# 3_-MCU.net
KiCad netlist of a schematic drawn in Altium Designer
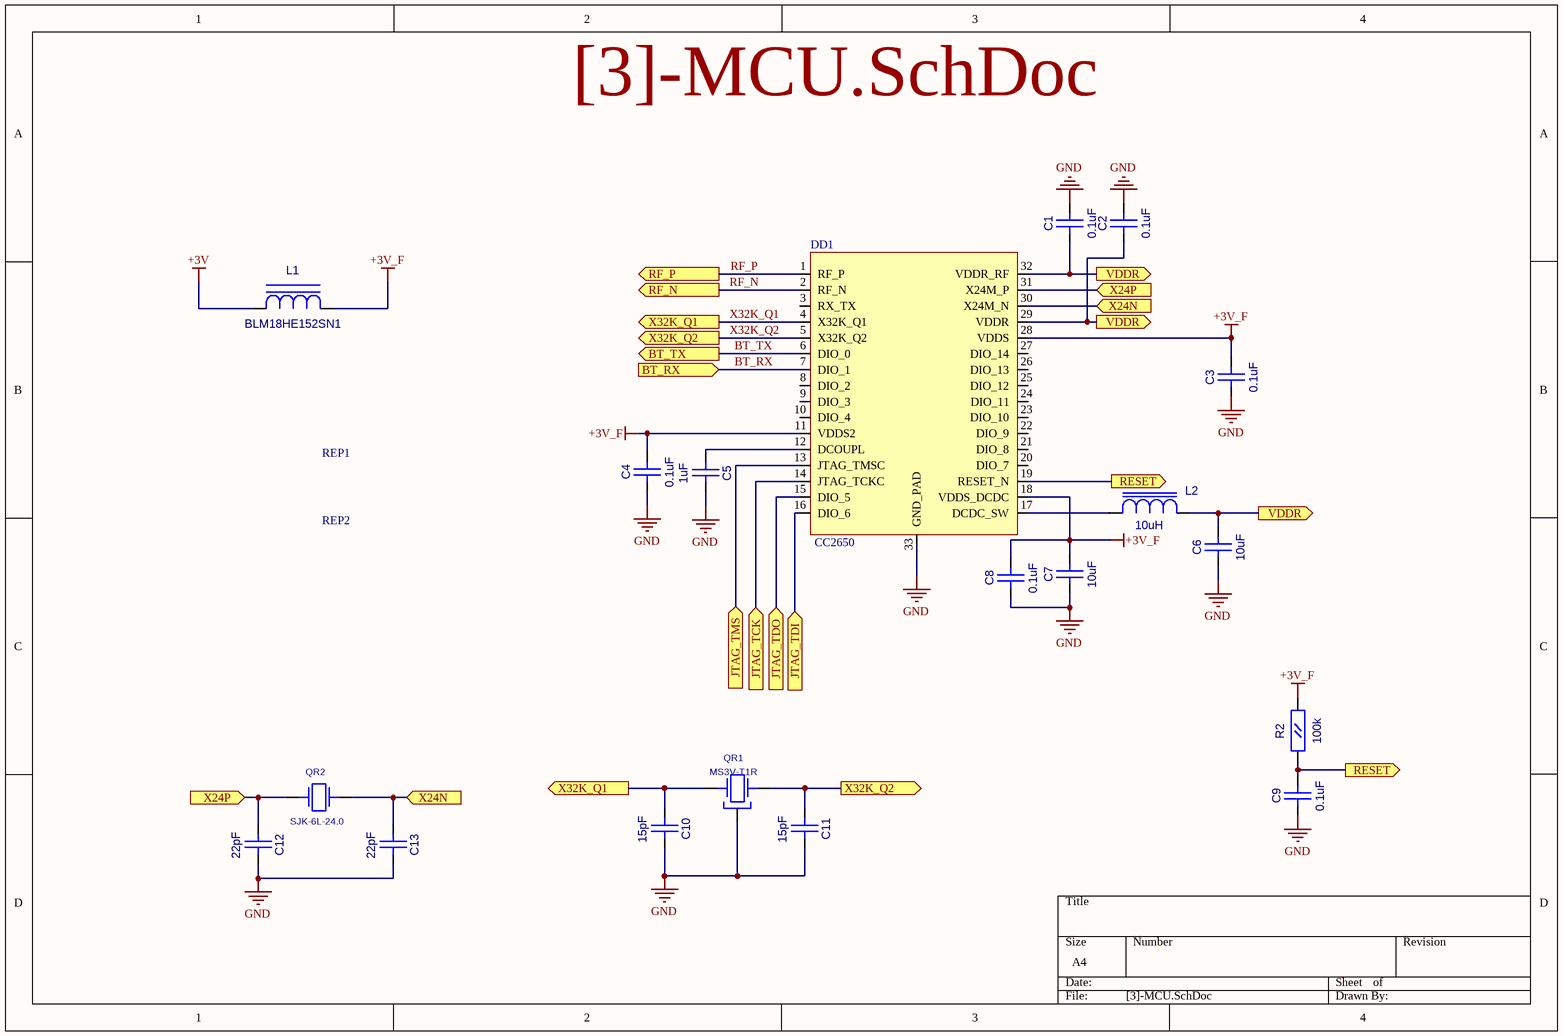
[diagram p0: [3]-MCU.SchDoc]

(export (version "E")
  (design (tool "Eeschema 10.0.6"))
  (components
    (comp (ref "C1")
      (value "0.1uF")
      (footprint "CC0603")
      (description "CC0603")
      (libsource (lib "gprs_modem_2") (part "CC0603"))
    )
    (comp (ref "C2")
      (value "0.1uF")
      (footprint "CC0603")
      (description "CC0603")
      (libsource (lib "gprs_modem_2") (part "CC0603"))
    )
    (comp (ref "C3")
      (value "0.1uF")
      (footprint "CC0603")
      (description "CC0603")
      (libsource (lib "gprs_modem_2") (part "CC0603"))
    )
    (comp (ref "C4")
      (value "0.1uF")
      (footprint "CC0603")
      (description "CC0603")
      (libsource (lib "gprs_modem_2") (part "CC0603"))
    )
    (comp (ref "C5")
      (value "1uF")
      (footprint "CC0603")
      (description "CC0603")
      (libsource (lib "gprs_modem_2") (part "CC0603"))
    )
    (comp (ref "C6")
      (value "10uF")
      (footprint "CC0805")
      (description "CC0805")
      (libsource (lib "gprs_modem_2") (part "CC0805"))
    )
    (comp (ref "C7")
      (value "10uF")
      (footprint "CC0805")
      (description "CC0805")
      (libsource (lib "gprs_modem_2") (part "CC0805"))
    )
    (comp (ref "C8")
      (value "0.1uF")
      (footprint "CC0603")
      (description "CC0603")
      (libsource (lib "gprs_modem_2") (part "CC0603"))
    )
    (comp (ref "C9")
      (value "0.1uF")
      (footprint "CC0603")
      (description "CC0603")
      (libsource (lib "gprs_modem_2") (part "CC0603"))
    )
    (comp (ref "C10")
      (value "15pF")
      (footprint "CC0603")
      (description "CC0603")
      (libsource (lib "gprs_modem_2") (part "CC0603"))
    )
    (comp (ref "C11")
      (value "15pF")
      (footprint "CC0603")
      (description "CC0603")
      (libsource (lib "gprs_modem_2") (part "CC0603"))
    )
    (comp (ref "C12")
      (value "22pF")
      (footprint "CC0603")
      (description "CC0603")
      (libsource (lib "gprs_modem_2") (part "CC0603"))
    )
    (comp (ref "C13")
      (value "22pF")
      (footprint "CC0603")
      (description "CC0603")
      (libsource (lib "gprs_modem_2") (part "CC0603"))
    )
    (comp (ref "DD1")
      (value "CC2650")
      (footprint "QFN32_TI")
      (description "CC2650RHBT")
      (libsource (lib "gprs_modem_2") (part "CC2650RHB"))
    )
    (comp (ref "L1")
      (value "BLM18HE152SN1")
      (footprint "L0603")
      (description "L0603")
      (libsource (lib "gprs_modem_2") (part "L0603"))
    )
    (comp (ref "L2")
      (value "10uH")
      (footprint "RC0805")
      (description "L0805")
      (libsource (lib "gprs_modem_2") (part "L0805"))
    )
    (comp (ref "QR1")
      (value "MS3V-T1R")
      (footprint "MS3V-T1R")
      (description "CRYSTAL_32768 Hz")
      (libsource (lib "gprs_modem_2") (part "MS3V-T1R"))
    )
    (comp (ref "QR2")
      (value "SJK-6L-24.0")
      (footprint "AC5032_2")
      (description "AC5032/2")
      (libsource (lib "gprs_modem_2") (part "AC5032_2"))
    )
    (comp (ref "R2")
      (value "100k")
      (footprint "RC0603")
      (description "RC0603")
      (libsource (lib "gprs_modem_2") (part "RC0603"))
    )
    (comp (ref "REP1")
      (value "REPER_POINT_1.2")
      (footprint "REPER1.2")
      (description "REPER1.2")
      (libsource (lib "fizik_lib") (part "REPER1.2"))
    )
    (comp (ref "REP2")
      (value "REPER_POINT_1.2")
      (footprint "REPER1.2")
      (description "REPER1.2")
      (libsource (lib "fizik_lib") (part "REPER1.2"))
    )
  )
  (nets
    (net (code "1") (name "+3V") (class "Default")
      (node (ref "L1") (pin "1") (pinfunction "A_1") (pintype "passive"))
    )
    (net (code "2") (name "+3V_F") (class "Default")
      (node (ref "C3") (pin "2") (pinfunction "B_2") (pintype "passive"))
      (node (ref "C4") (pin "2") (pinfunction "B_2") (pintype "passive"))
      (node (ref "C7") (pin "2") (pinfunction "B_2") (pintype "passive"))
      (node (ref "C8") (pin "2") (pinfunction "B_2") (pintype "passive"))
      (node (ref "DD1") (pin "11") (pinfunction "VDDS2_11") (pintype "passive"))
      (node (ref "DD1") (pin "18") (pinfunction "VDDS_DCDC_18") (pintype "passive"))
      (node (ref "DD1") (pin "28") (pinfunction "VDDS_28") (pintype "passive"))
      (node (ref "L1") (pin "2") (pinfunction "C_2") (pintype "passive"))
      (node (ref "R2") (pin "2") (pinfunction "B_2") (pintype "passive"))
    )
    (net (code "3") (name "/BT_RX") (class "Default")
      (node (ref "DD1") (pin "7") (pinfunction "DIO_1_7") (pintype "passive"))
    )
    (net (code "4") (name "/BT_TX") (class "Default")
      (node (ref "DD1") (pin "6") (pinfunction "DIO_0_6") (pintype "passive"))
    )
    (net (code "5") (name "/JTAG_TCK") (class "Default")
      (node (ref "DD1") (pin "14") (pinfunction "JTAG_TCKC_14") (pintype "passive"))
    )
    (net (code "6") (name "/JTAG_TDI") (class "Default")
      (node (ref "DD1") (pin "16") (pinfunction "DIO_6_16") (pintype "passive"))
    )
    (net (code "7") (name "/JTAG_TDO") (class "Default")
      (node (ref "DD1") (pin "15") (pinfunction "DIO_5_15") (pintype "passive"))
    )
    (net (code "8") (name "/JTAG_TMS") (class "Default")
      (node (ref "DD1") (pin "13") (pinfunction "JTAG_TMSC_13") (pintype "passive"))
    )
    (net (code "9") (name "/RESET") (class "Default")
      (node (ref "C9") (pin "2") (pinfunction "B_2") (pintype "passive"))
      (node (ref "DD1") (pin "19") (pinfunction "RESET_N_19") (pintype "passive"))
      (node (ref "R2") (pin "1") (pinfunction "A_1") (pintype "passive"))
    )
    (net (code "10") (name "/RF_N") (class "Default")
      (node (ref "DD1") (pin "2") (pinfunction "RF_N_2") (pintype "passive"))
    )
    (net (code "11") (name "/RF_P") (class "Default")
      (node (ref "DD1") (pin "1") (pinfunction "RF_P_1") (pintype "passive"))
    )
    (net (code "12") (name "/VDDR") (class "Default")
      (node (ref "C1") (pin "1") (pinfunction "A_1") (pintype "passive"))
      (node (ref "C2") (pin "1") (pinfunction "A_1") (pintype "passive"))
      (node (ref "C6") (pin "2") (pinfunction "B_2") (pintype "passive"))
      (node (ref "DD1") (pin "29") (pinfunction "VDDR_29") (pintype "passive"))
      (node (ref "DD1") (pin "32") (pinfunction "VDDR_RF_32") (pintype "passive"))
      (node (ref "L2") (pin "2") (pinfunction "B_2") (pintype "passive"))
    )
    (net (code "13") (name "/X24N") (class "Default")
      (node (ref "C13") (pin "1") (pinfunction "A_1") (pintype "passive"))
      (node (ref "DD1") (pin "30") (pinfunction "X24M_N_30") (pintype "passive"))
      (node (ref "QR2") (pin "2") (pintype "passive"))
    )
    (net (code "14") (name "/X24P") (class "Default")
      (node (ref "C12") (pin "1") (pinfunction "A_1") (pintype "passive"))
      (node (ref "DD1") (pin "31") (pinfunction "X24M_P_31") (pintype "passive"))
      (node (ref "QR2") (pin "1") (pintype "passive"))
    )
    (net (code "15") (name "/X32K_Q1") (class "Default")
      (node (ref "C10") (pin "1") (pinfunction "A_1") (pintype "passive"))
      (node (ref "DD1") (pin "4") (pinfunction "X32K_Q1_4") (pintype "passive"))
      (node (ref "QR1") (pin "2") (pinfunction "X2_2") (pintype "passive"))
    )
    (net (code "16") (name "/X32K_Q2") (class "Default")
      (node (ref "C11") (pin "1") (pinfunction "A_1") (pintype "passive"))
      (node (ref "DD1") (pin "5") (pinfunction "X32K_Q2_5") (pintype "passive"))
      (node (ref "QR1") (pin "1") (pinfunction "X1_1") (pintype "passive"))
    )
    (net (code "17") (name "GND") (class "Default")
      (node (ref "C1") (pin "2") (pinfunction "B_2") (pintype "passive"))
      (node (ref "C10") (pin "2") (pinfunction "B_2") (pintype "passive"))
      (node (ref "C11") (pin "2") (pinfunction "B_2") (pintype "passive"))
      (node (ref "C12") (pin "2") (pinfunction "B_2") (pintype "passive"))
      (node (ref "C13") (pin "2") (pinfunction "B_2") (pintype "passive"))
      (node (ref "C2") (pin "2") (pinfunction "B_2") (pintype "passive"))
      (node (ref "C3") (pin "1") (pinfunction "A_1") (pintype "passive"))
      (node (ref "C4") (pin "1") (pinfunction "A_1") (pintype "passive"))
      (node (ref "C5") (pin "2") (pinfunction "B_2") (pintype "passive"))
      (node (ref "C6") (pin "1") (pinfunction "A_1") (pintype "passive"))
      (node (ref "C7") (pin "1") (pinfunction "A_1") (pintype "passive"))
      (node (ref "C8") (pin "1") (pinfunction "A_1") (pintype "passive"))
      (node (ref "C9") (pin "1") (pinfunction "A_1") (pintype "passive"))
      (node (ref "DD1") (pin "33") (pinfunction "GND_PAD_33") (pintype "passive"))
      (node (ref "QR1") (pin "3") (pinfunction "3_3") (pintype "passive"))
    )
    (net (code "18") (name "Net-(C5-A)") (class "Default")
      (node (ref "C5") (pin "1") (pinfunction "A_1") (pintype "passive"))
      (node (ref "DD1") (pin "12") (pinfunction "DCOUPL_12") (pintype "passive"))
    )
    (net (code "19") (name "Net-(DD1-DCDC_SW)") (class "Default")
      (node (ref "DD1") (pin "17") (pinfunction "DCDC_SW_17") (pintype "passive"))
      (node (ref "L2") (pin "1") (pinfunction "A_1") (pintype "passive"))
    )
    (net (code "20") (name "unconnected-(DD1-DIO_2-Pad8)") (class "Default")
      (node (ref "DD1") (pin "8") (pinfunction "DIO_2_8") (pintype "passive"))
    )
    (net (code "21") (name "unconnected-(DD1-DIO_3-Pad9)") (class "Default")
      (node (ref "DD1") (pin "9") (pinfunction "DIO_3_9") (pintype "passive"))
    )
    (net (code "22") (name "unconnected-(DD1-DIO_4-Pad10)") (class "Default")
      (node (ref "DD1") (pin "10") (pinfunction "DIO_4_10") (pintype "passive"))
    )
    (net (code "23") (name "unconnected-(DD1-DIO_7-Pad20)") (class "Default")
      (node (ref "DD1") (pin "20") (pinfunction "DIO_7_20") (pintype "passive"))
    )
    (net (code "24") (name "unconnected-(DD1-DIO_8-Pad21)") (class "Default")
      (node (ref "DD1") (pin "21") (pinfunction "DIO_8_21") (pintype "passive"))
    )
    (net (code "25") (name "unconnected-(DD1-DIO_9-Pad22)") (class "Default")
      (node (ref "DD1") (pin "22") (pinfunction "DIO_9_22") (pintype "passive"))
    )
    (net (code "26") (name "unconnected-(DD1-DIO_10-Pad23)") (class "Default")
      (node (ref "DD1") (pin "23") (pinfunction "DIO_10_23") (pintype "passive"))
    )
    (net (code "27") (name "unconnected-(DD1-DIO_11-Pad24)") (class "Default")
      (node (ref "DD1") (pin "24") (pinfunction "DIO_11_24") (pintype "passive"))
    )
    (net (code "28") (name "unconnected-(DD1-DIO_12-Pad25)") (class "Default")
      (node (ref "DD1") (pin "25") (pinfunction "DIO_12_25") (pintype "passive"))
    )
    (net (code "29") (name "unconnected-(DD1-DIO_13-Pad26)") (class "Default")
      (node (ref "DD1") (pin "26") (pinfunction "DIO_13_26") (pintype "passive"))
    )
    (net (code "30") (name "unconnected-(DD1-DIO_14-Pad27)") (class "Default")
      (node (ref "DD1") (pin "27") (pinfunction "DIO_14_27") (pintype "passive"))
    )
    (net (code "31") (name "unconnected-(DD1-RX_TX-Pad3)") (class "Default")
      (node (ref "DD1") (pin "3") (pinfunction "RX_TX_3") (pintype "passive"))
    )
    (net (code "32") (name "unconnected-(REP1-Pad1)") (class "Default")
      (node (ref "REP1") (pin "1") (pintype "passive"))
    )
    (net (code "33") (name "unconnected-(REP2-Pad1)") (class "Default")
      (node (ref "REP2") (pin "1") (pintype "passive"))
    )
  )
)
